# P-FTINT-2-0.net
KiCad netlist of a schematic drawn in Altium Designer
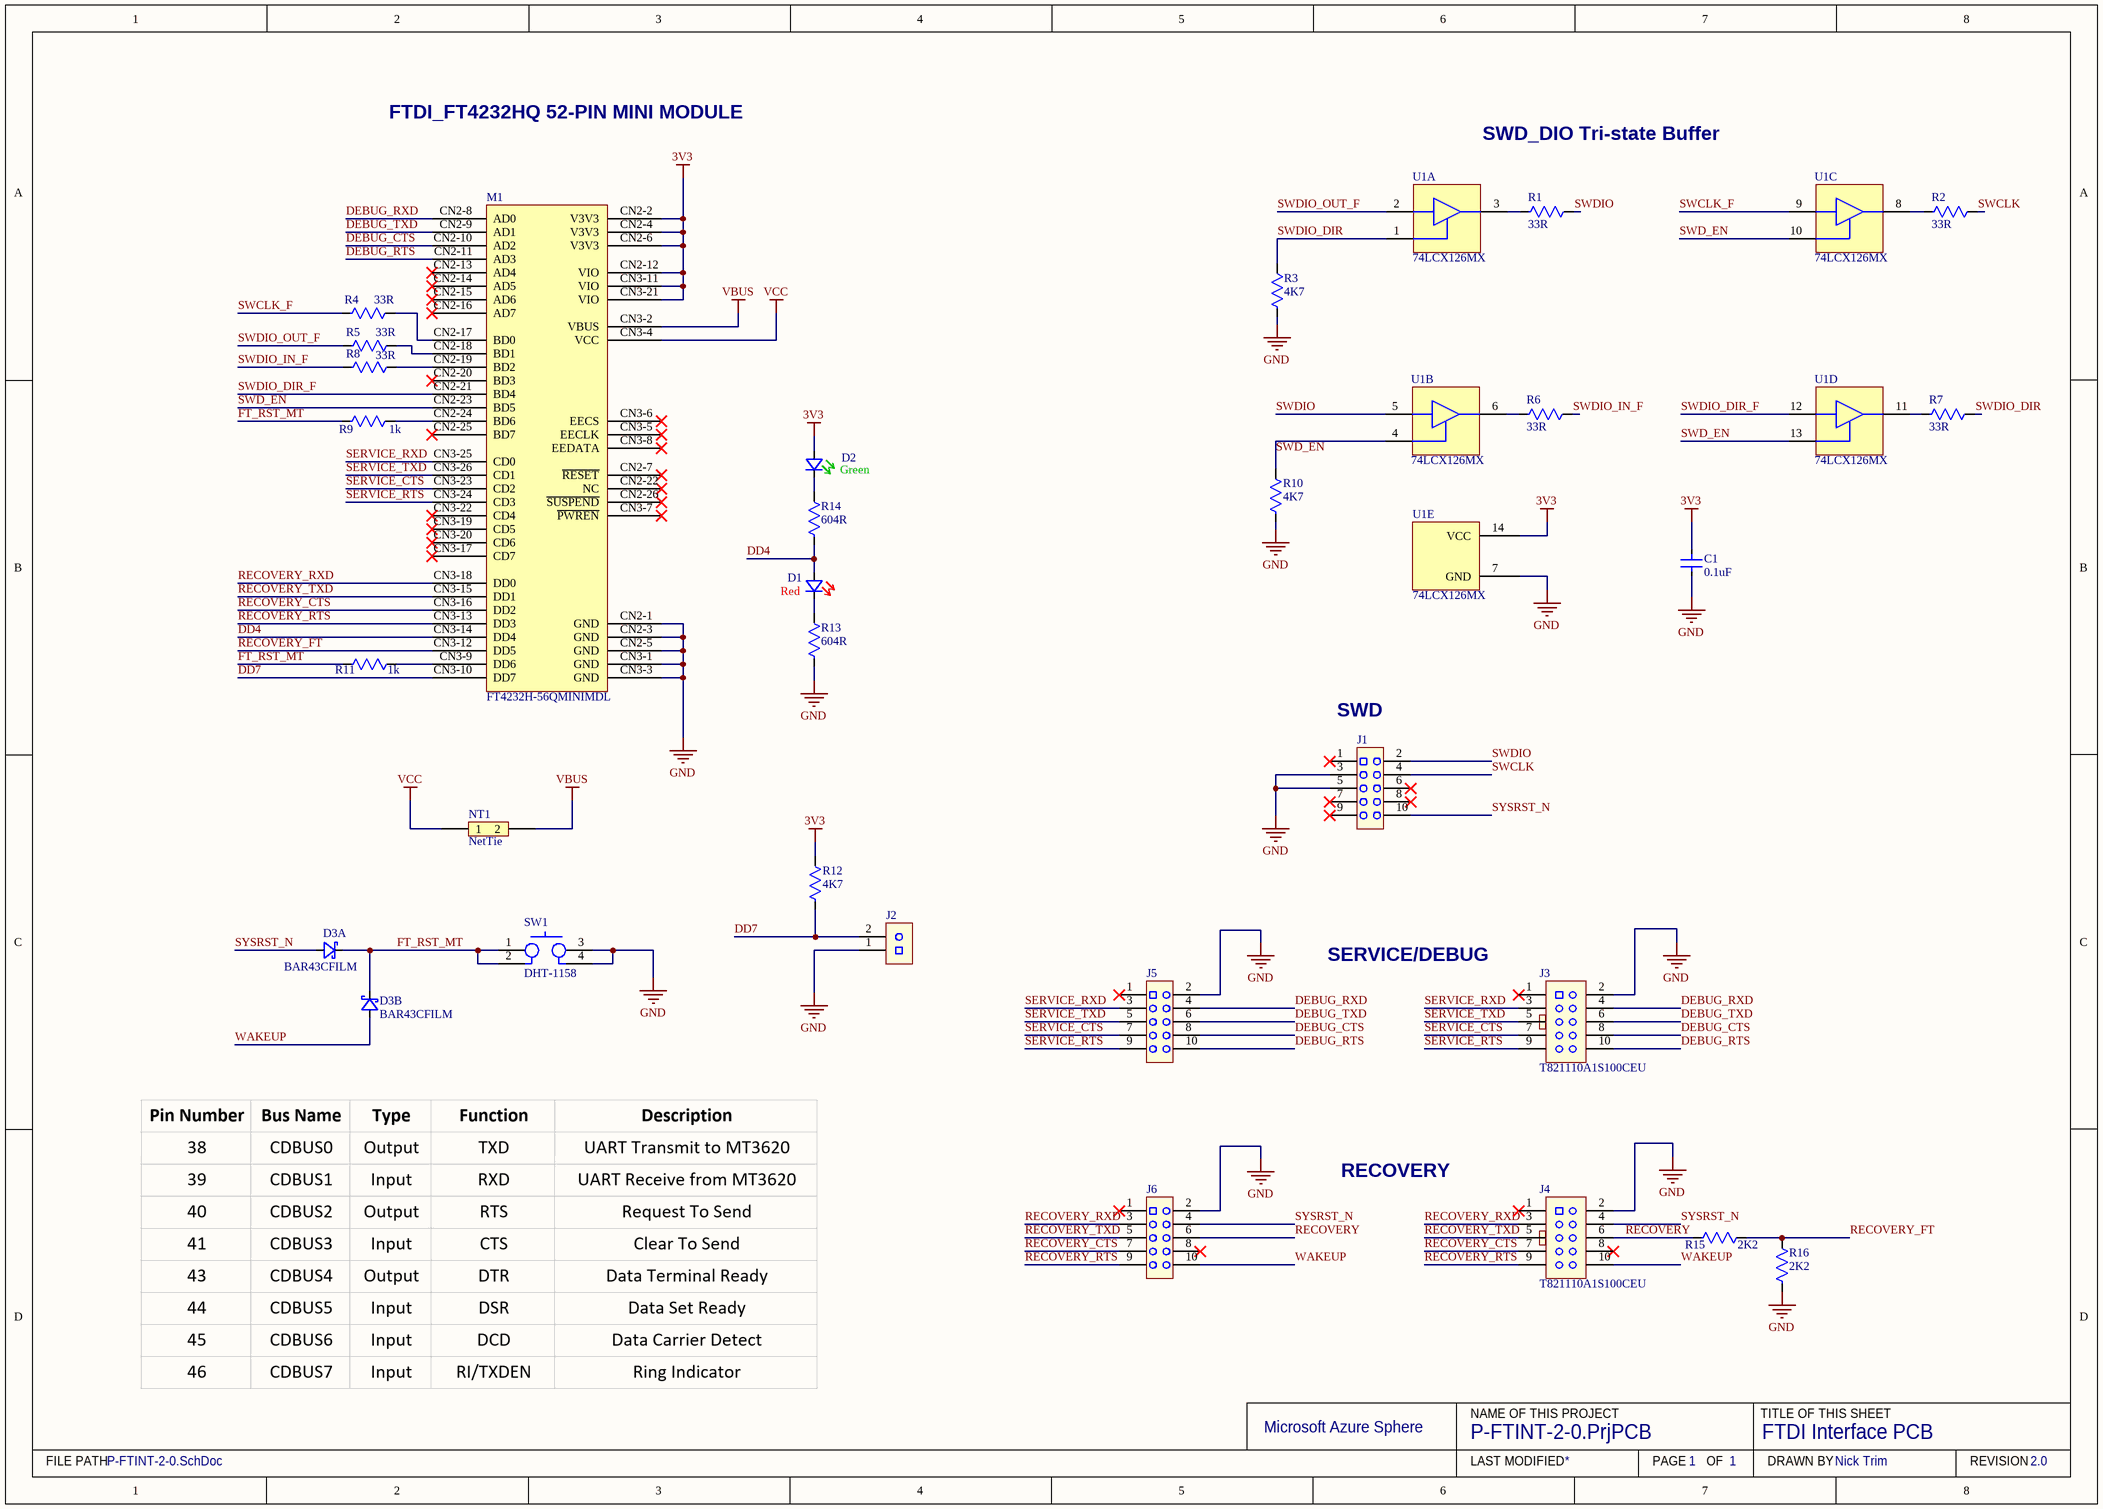
[diagram p0: P-FTINT-2-0.SchDoc]

(export (version "E")
  (design (tool "Eeschema 10.0.6"))
  (components
    (comp (ref "C1")
      (value "0.1uF")
      (footprint "CAP 0603 (1608) x 1.2mm")
      (description "CAP CER 0.1UF 25V X7R 0603")
      (fields
        (field (name "MANUFACTURER") "TDK")
        (field (name "MANUFACTURER PART NUMBER") "CGA3E2X7R1E104K080AA")
      )
      (libsource (lib "TDK-Capacitor_C_0603") (part "CGA3E2X7R1E104K080AA"))
    )
    (comp (ref "D1")
      (value "SML-D12U")
      (footprint "Rohm SML-D12 Red")
      (description "1.6 x 0.8 x 0.55mm (0603) LED 620nm Red")
      (fields
        (field (name "MANUFACTURER") "Rohm Semiconductor")
        (field (name "MANUFACTURER PART NUMBER") "SML-D12U8WT86")
        (field (name "COLOUR") "Red")
      )
      (libsource (lib "Rohm") (part "SML-D12U"))
    )
    (comp (ref "D2")
      (value "SML-D12P")
      (footprint "Rohm SML-D12 Green")
      (description "1.6 x 0.8 x 0.55mm (0603) LED 560nm Green")
      (fields
        (field (name "MANUFACTURER") "Rohm Semiconductor")
        (field (name "MANUFACTURER PART NUMBER") "SML-D12P8WT86")
        (field (name "COLOUR") "Green")
      )
      (libsource (lib "Rohm") (part "SML-D12P"))
    )
    (comp (ref "D3")
      (value "BAR43CFILM")
      (footprint "ON_SEMI-SOT23-3")
      (description "Small Signal Schottky Diode, Dual Common Cathode, 30 V, 100 mA, 330 mV, 750 mA, 150 °C")
      (fields (field (name "MANUFACTURER") "STMicroelectronics"))
      (libsource (lib "ST") (part "BAR43CFILM"))
    )
    (comp (ref "J1")
      (value "FTSH-105-01-F-DV-K")
      (footprint "SAMTEC-FTSH-105-01-X-DV-K")
      (description "CONN HEADER 10POS DUAL .05\" SMD")
      (fields (field (name "MANUFACTURER") "Samtec Inc."))
      (libsource (lib "Samtec") (part "FTSH-105-01-F-DV-K"))
    )
    (comp (ref "J2")
      (value "MOLEX-0022284020")
      (footprint "0022284020")
      (description "CONN HEADER 2POS .100 VERT TIN")
      (fields
        (field (name "MANUFACTURER") "Molex, LLC")
        (field (name "MANUFACTURER PART NUMBER") "0022284020")
      )
      (libsource (lib "Molex") (part "MOLEX-0022284020"))
    )
    (comp (ref "J3")
      (value "T821110A1S100CEU")
      (footprint "10 way shrouded IDC HDR:10 Way shrouded IDC hdr")
      (description "Conn Shrouded Header HDR 10 POS 2.54mm Solder ST Thru-Hole")
      (fields
        (field (name "MANUFACTURER") "Amphenol")
        (field (name "MANUFACTURER PART NUMBER") "T821110A1S100CEU")
      )
      (libsource (lib "Amphenol") (part "T821110A1S100CEU"))
    )
    (comp (ref "J4")
      (value "T821110A1S100CEU")
      (footprint "10 way shrouded IDC HDR:10 Way shrouded IDC hdr")
      (description "Conn Shrouded Header HDR 10 POS 2.54mm Solder ST Thru-Hole")
      (fields
        (field (name "MANUFACTURER") "Amphenol")
        (field (name "MANUFACTURER PART NUMBER") "T821110A1S100CEU")
      )
      (libsource (lib "Amphenol") (part "T821110A1S100CEU"))
    )
    (comp (ref "J5")
      (value "FTSH-105-01-F-DV-K")
      (footprint "SAMTEC-FTSH-105-01-X-DV-K")
      (description "CONN HEADER 10POS DUAL .05\" SMD")
      (fields (field (name "MANUFACTURER") "Samtec Inc."))
      (libsource (lib "Samtec") (part "FTSH-105-01-F-DV-K"))
    )
    (comp (ref "J6")
      (value "FTSH-105-01-F-DV-K")
      (footprint "SAMTEC-FTSH-105-01-X-DV-K")
      (description "CONN HEADER 10POS DUAL .05\" SMD")
      (fields (field (name "MANUFACTURER") "Samtec Inc."))
      (libsource (lib "Samtec") (part "FTSH-105-01-F-DV-K"))
    )
    (comp (ref "M1")
      (value "FT4232H-56QMINIMDL")
      (footprint "FT4232H-56Q")
      (description "IC MINI MODULE USB/FIFO 56QFN")
      (fields (field (name "MANUFACTURER") "FTDI"))
      (libsource (lib "FTDI") (part "FT4232H-56QMINIMDL"))
    )
    (comp (ref "NT1") (value "NetTie") (footprint "NetTie") (libsource (lib "generic") (part "NetTie")))
    (comp (ref "R1")
      (value "33R")
      (footprint "RES0603")
      (description "RES SMD 33 OHM 5% 1/10W 0603")
      (fields
        (field (name "MANUFACTURER") "Panasonic")
        (field (name "MANUFACTURER PART NUMBER") "ERJ-3GEYJ330V")
      )
      (libsource (lib "Panasonic_Resistor_ERJ3GR_0603") (part "ERJ-3GEYJ330V"))
    )
    (comp (ref "R2")
      (value "33R")
      (footprint "RES0603")
      (description "RES SMD 33 OHM 5% 1/10W 0603")
      (fields
        (field (name "MANUFACTURER") "Panasonic")
        (field (name "MANUFACTURER PART NUMBER") "ERJ-3GEYJ330V")
      )
      (libsource (lib "Panasonic_Resistor_ERJ3GR_0603") (part "ERJ-3GEYJ330V"))
    )
    (comp (ref "R3")
      (value "4K7")
      (footprint "RES0603")
      (description "RES SMD 4.7K OHM 5% 1/10W 0603")
      (fields
        (field (name "MANUFACTURER") "Panasonic")
        (field (name "MANUFACTURER PART NUMBER") "ERJ-3GEYJ472V")
      )
      (libsource (lib "Panasonic_Resistor_ERJ3GR_0603") (part "ERJ-3GEYJ472V"))
    )
    (comp (ref "R4")
      (value "33R")
      (footprint "RES0603")
      (description "RES SMD 33 OHM 5% 1/10W 0603")
      (fields
        (field (name "MANUFACTURER") "Panasonic")
        (field (name "MANUFACTURER PART NUMBER") "ERJ-3GEYJ330V")
      )
      (libsource (lib "Panasonic_Resistor_ERJ3GR_0603") (part "ERJ-3GEYJ330V"))
    )
    (comp (ref "R5")
      (value "33R")
      (footprint "RES0603")
      (description "RES SMD 33 OHM 5% 1/10W 0603")
      (fields
        (field (name "MANUFACTURER") "Panasonic")
        (field (name "MANUFACTURER PART NUMBER") "ERJ-3GEYJ330V")
      )
      (libsource (lib "Panasonic_Resistor_ERJ3GR_0603") (part "ERJ-3GEYJ330V"))
    )
    (comp (ref "R6")
      (value "33R")
      (footprint "RES0603")
      (description "RES SMD 33 OHM 5% 1/10W 0603")
      (fields
        (field (name "MANUFACTURER") "Panasonic")
        (field (name "MANUFACTURER PART NUMBER") "ERJ-3GEYJ330V")
      )
      (libsource (lib "Panasonic_Resistor_ERJ3GR_0603") (part "ERJ-3GEYJ330V"))
    )
    (comp (ref "R7")
      (value "33R")
      (footprint "RES0603")
      (description "RES SMD 33 OHM 5% 1/10W 0603")
      (fields
        (field (name "MANUFACTURER") "Panasonic")
        (field (name "MANUFACTURER PART NUMBER") "ERJ-3GEYJ330V")
      )
      (libsource (lib "Panasonic_Resistor_ERJ3GR_0603") (part "ERJ-3GEYJ330V"))
    )
    (comp (ref "R8")
      (value "33R")
      (footprint "RES0603")
      (description "RES SMD 33 OHM 5% 1/10W 0603")
      (fields
        (field (name "MANUFACTURER") "Panasonic")
        (field (name "MANUFACTURER PART NUMBER") "ERJ-3GEYJ330V")
      )
      (libsource (lib "Panasonic_Resistor_ERJ3GR_0603") (part "ERJ-3GEYJ330V"))
    )
    (comp (ref "R9")
      (value "ERJ-PA3J102V")
      (footprint "RES0603")
      (description "RES SMD 1K OHM 5% 1/10W 0603")
      (fields
        (field (name "MANUFACTURER") "Panasonic")
        (field (name "RESISTANCE") "1k")
        (field (name "TOLERANCE") "5%")
      )
      (libsource (lib "Panasonic_Resistor_ERJ3GR_0603") (part "ERJ-PA3J102V"))
    )
    (comp (ref "R10")
      (value "4K7")
      (footprint "RES0603")
      (description "RES SMD 4.7K OHM 5% 1/10W 0603")
      (fields
        (field (name "MANUFACTURER") "Panasonic")
        (field (name "MANUFACTURER PART NUMBER") "ERJ-3GEYJ472V")
      )
      (libsource (lib "Panasonic_Resistor_ERJ3GR_0603") (part "ERJ-3GEYJ472V"))
    )
    (comp (ref "R11")
      (value "ERJ-PA3J102V")
      (footprint "RES0603")
      (description "RES SMD 1K OHM 5% 1/10W 0603")
      (fields
        (field (name "MANUFACTURER") "Panasonic")
        (field (name "RESISTANCE") "1k")
        (field (name "TOLERANCE") "5%")
      )
      (libsource (lib "Panasonic_Resistor_ERJ3GR_0603") (part "ERJ-PA3J102V"))
    )
    (comp (ref "R12")
      (value "4K7")
      (footprint "RES0603")
      (description "RES SMD 4.7K OHM 5% 1/10W 0603")
      (fields
        (field (name "MANUFACTURER") "Panasonic")
        (field (name "MANUFACTURER PART NUMBER") "ERJ-3GEYJ472V")
      )
      (libsource (lib "Panasonic_Resistor_ERJ3GR_0603") (part "ERJ-3GEYJ472V"))
    )
    (comp (ref "R13")
      (value "604R")
      (footprint "RES0603")
      (description "RES SMD 604 OHM 1% 1/10W 0603")
      (fields
        (field (name "MANUFACTURER") "Panasonic")
        (field (name "MANUFACTURER PART NUMBER") "ERJ-3EKF6040V")
      )
      (libsource (lib "Panasonic_Resistor_ERJ3GR_0603") (part "ERJ-3EKF6040V"))
    )
    (comp (ref "R14")
      (value "604R")
      (footprint "RES0603")
      (description "RES SMD 604 OHM 1% 1/10W 0603")
      (fields
        (field (name "MANUFACTURER") "Panasonic")
        (field (name "MANUFACTURER PART NUMBER") "ERJ-3EKF6040V")
      )
      (libsource (lib "Panasonic_Resistor_ERJ3GR_0603") (part "ERJ-3EKF6040V"))
    )
    (comp (ref "R15")
      (value "2K2")
      (footprint "RES0603")
      (description "RES SMD 2.2K OHM 5% 1/10W 0603")
      (fields
        (field (name "MANUFACTURER") "Panasonic")
        (field (name "MANUFACTURER PART NUMBER") "ERJ-3GEYJ222V")
      )
      (libsource (lib "Panasonic_Resistor_ERJ3GR_0603") (part "ERJ-3GEYJ222V"))
    )
    (comp (ref "R16")
      (value "2K2")
      (footprint "RES0603")
      (description "RES SMD 2.2K OHM 5% 1/10W 0603")
      (fields
        (field (name "MANUFACTURER") "Panasonic")
        (field (name "MANUFACTURER PART NUMBER") "ERJ-3GEYJ222V")
      )
      (libsource (lib "Panasonic_Resistor_ERJ3GR_0603") (part "ERJ-3GEYJ222V"))
    )
    (comp (ref "SW1") (value "DHT-1158") (footprint "DHT-1158") (libsource (lib "Seeed") (part "DHT-1158")))
    (comp (ref "U1")
      (value "74LCX126MX")
      (footprint "74LCX126MX")
      (description "Buffers & Line Drivers LV Quad Buffer 5V Tolerant I/O")
      (fields (field (name "MANUFACTURER") "ON Semiconductor / Fairchild"))
      (libsource (lib "OnSemiconductor") (part "74LCX126MX"))
    )
  )
  (nets
    (net (code "1") (name "/DD4") (class "Default")
      (node (ref "D1") (pin "2") (pinfunction "A_2") (pintype "passive"))
      (node (ref "M1") (pin "CN3-14") (pinfunction "DD4_CN3-14") (pintype "passive"))
      (node (ref "R14") (pin "2") (pinfunction "2_2") (pintype "passive"))
    )
    (net (code "2") (name "/DD7") (class "Default")
      (node (ref "J2") (pin "2") (pinfunction "2_2") (pintype "passive"))
      (node (ref "M1") (pin "CN3-10") (pinfunction "DD7_CN3-10") (pintype "passive"))
      (node (ref "R12") (pin "2") (pinfunction "2_2") (pintype "passive"))
    )
    (net (code "3") (name "/DEBUG_CTS") (class "Default")
      (node (ref "J3") (pin "8") (pinfunction "8_8") (pintype "passive"))
      (node (ref "J5") (pin "8") (pinfunction "8_8") (pintype "passive"))
      (node (ref "M1") (pin "CN2-10") (pinfunction "AD2_CN2-10") (pintype "passive"))
    )
    (net (code "4") (name "/DEBUG_RTS") (class "Default")
      (node (ref "J3") (pin "10") (pinfunction "10_10") (pintype "passive"))
      (node (ref "J5") (pin "10") (pinfunction "10_10") (pintype "passive"))
      (node (ref "M1") (pin "CN2-11") (pinfunction "AD3_CN2-11") (pintype "passive"))
    )
    (net (code "5") (name "/DEBUG_RXD") (class "Default")
      (node (ref "J3") (pin "4") (pinfunction "4_4") (pintype "passive"))
      (node (ref "J5") (pin "4") (pinfunction "4_4") (pintype "passive"))
      (node (ref "M1") (pin "CN2-8") (pinfunction "AD0_CN2-8") (pintype "passive"))
    )
    (net (code "6") (name "/DEBUG_TXD") (class "Default")
      (node (ref "J3") (pin "6") (pinfunction "6_6") (pintype "passive"))
      (node (ref "J5") (pin "6") (pinfunction "6_6") (pintype "passive"))
      (node (ref "M1") (pin "CN2-9") (pinfunction "AD1_CN2-9") (pintype "passive"))
    )
    (net (code "7") (name "/FT_RST_MT") (class "Default")
      (node (ref "D3") (pin "3") (pinfunction "K_3") (pintype "passive"))
      (node (ref "R11") (pin "2") (pinfunction "2_2") (pintype "passive"))
      (node (ref "R9") (pin "2") (pinfunction "2_2") (pintype "passive"))
      (node (ref "SW1") (pin "1") (pinfunction "1_1") (pintype "passive"))
      (node (ref "SW1") (pin "2") (pinfunction "2_2") (pintype "passive"))
    )
    (net (code "8") (name "/RECOVERY") (class "Default")
      (node (ref "J4") (pin "6") (pinfunction "6_6") (pintype "passive"))
      (node (ref "J6") (pin "6") (pinfunction "6_6") (pintype "passive"))
      (node (ref "R15") (pin "2") (pinfunction "2_2") (pintype "passive"))
    )
    (net (code "9") (name "/RECOVERY_CTS") (class "Default")
      (node (ref "J4") (pin "7") (pinfunction "7_7") (pintype "passive"))
      (node (ref "J6") (pin "7") (pinfunction "7_7") (pintype "passive"))
      (node (ref "M1") (pin "CN3-16") (pinfunction "DD2_CN3-16") (pintype "passive"))
    )
    (net (code "10") (name "/RECOVERY_FT") (class "Default")
      (node (ref "M1") (pin "CN3-12") (pinfunction "DD5_CN3-12") (pintype "passive"))
      (node (ref "R15") (pin "1") (pinfunction "1_1") (pintype "passive"))
      (node (ref "R16") (pin "1") (pinfunction "1_1") (pintype "passive"))
    )
    (net (code "11") (name "/RECOVERY_RTS") (class "Default")
      (node (ref "J4") (pin "9") (pinfunction "9_9") (pintype "passive"))
      (node (ref "J6") (pin "9") (pinfunction "9_9") (pintype "passive"))
      (node (ref "M1") (pin "CN3-13") (pinfunction "DD3_CN3-13") (pintype "passive"))
    )
    (net (code "12") (name "/RECOVERY_RXD") (class "Default")
      (node (ref "J4") (pin "3") (pinfunction "3_3") (pintype "passive"))
      (node (ref "J6") (pin "3") (pinfunction "3_3") (pintype "passive"))
      (node (ref "M1") (pin "CN3-18") (pinfunction "DD0_CN3-18") (pintype "passive"))
    )
    (net (code "13") (name "/RECOVERY_TXD") (class "Default")
      (node (ref "J4") (pin "5") (pinfunction "5_5") (pintype "passive"))
      (node (ref "J6") (pin "5") (pinfunction "5_5") (pintype "passive"))
      (node (ref "M1") (pin "CN3-15") (pinfunction "DD1_CN3-15") (pintype "passive"))
    )
    (net (code "14") (name "/SERVICE_CTS") (class "Default")
      (node (ref "J3") (pin "7") (pinfunction "7_7") (pintype "passive"))
      (node (ref "J5") (pin "7") (pinfunction "7_7") (pintype "passive"))
      (node (ref "M1") (pin "CN3-23") (pinfunction "CD2_CN3-23") (pintype "passive"))
    )
    (net (code "15") (name "/SERVICE_RTS") (class "Default")
      (node (ref "J3") (pin "9") (pinfunction "9_9") (pintype "passive"))
      (node (ref "J5") (pin "9") (pinfunction "9_9") (pintype "passive"))
      (node (ref "M1") (pin "CN3-24") (pinfunction "CD3_CN3-24") (pintype "passive"))
    )
    (net (code "16") (name "/SERVICE_RXD") (class "Default")
      (node (ref "J3") (pin "3") (pinfunction "3_3") (pintype "passive"))
      (node (ref "J5") (pin "3") (pinfunction "3_3") (pintype "passive"))
      (node (ref "M1") (pin "CN3-25") (pinfunction "CD0_CN3-25") (pintype "passive"))
    )
    (net (code "17") (name "/SERVICE_TXD") (class "Default")
      (node (ref "J3") (pin "5") (pinfunction "5_5") (pintype "passive"))
      (node (ref "J5") (pin "5") (pinfunction "5_5") (pintype "passive"))
      (node (ref "M1") (pin "CN3-26") (pinfunction "CD1_CN3-26") (pintype "passive"))
    )
    (net (code "18") (name "/SWCLK") (class "Default")
      (node (ref "J1") (pin "4") (pinfunction "4_4") (pintype "passive"))
      (node (ref "R2") (pin "1") (pinfunction "1_1") (pintype "passive"))
    )
    (net (code "19") (name "/SWCLK_F") (class "Default")
      (node (ref "R4") (pin "2") (pinfunction "2_2") (pintype "passive"))
      (node (ref "U1") (pin "9") (pinfunction "3A_9") (pintype "passive"))
    )
    (net (code "20") (name "/SWDIO") (class "Default")
      (node (ref "J1") (pin "2") (pinfunction "2_2") (pintype "passive"))
      (node (ref "R1") (pin "1") (pinfunction "1_1") (pintype "passive"))
      (node (ref "U1") (pin "5") (pinfunction "2A_5") (pintype "passive"))
    )
    (net (code "21") (name "/SWDIO_DIR") (class "Default")
      (node (ref "R3") (pin "1") (pinfunction "1_1") (pintype "passive"))
      (node (ref "R7") (pin "1") (pinfunction "1_1") (pintype "passive"))
      (node (ref "U1") (pin "1") (pinfunction "1OE_1") (pintype "passive"))
    )
    (net (code "22") (name "/SWDIO_DIR_F") (class "Default")
      (node (ref "M1") (pin "CN2-21") (pinfunction "BD4_CN2-21") (pintype "passive"))
      (node (ref "U1") (pin "12") (pinfunction "4A_12") (pintype "passive"))
    )
    (net (code "23") (name "/SWDIO_IN_F") (class "Default")
      (node (ref "R6") (pin "1") (pinfunction "1_1") (pintype "passive"))
      (node (ref "R8") (pin "2") (pinfunction "2_2") (pintype "passive"))
    )
    (net (code "24") (name "/SWDIO_OUT_F") (class "Default")
      (node (ref "R5") (pin "2") (pinfunction "2_2") (pintype "passive"))
      (node (ref "U1") (pin "2") (pinfunction "1A_2") (pintype "passive"))
    )
    (net (code "25") (name "/SWD_EN") (class "Default")
      (node (ref "M1") (pin "CN2-23") (pinfunction "BD5_CN2-23") (pintype "passive"))
      (node (ref "R10") (pin "1") (pinfunction "1_1") (pintype "passive"))
      (node (ref "U1") (pin "10") (pinfunction "3OE_10") (pintype "passive"))
      (node (ref "U1") (pin "13") (pinfunction "4OE_13") (pintype "passive"))
      (node (ref "U1") (pin "4") (pinfunction "2OE_4") (pintype "passive"))
    )
    (net (code "26") (name "/SYSRST_N") (class "Default")
      (node (ref "D3") (pin "1") (pinfunction "A1_1") (pintype "passive"))
      (node (ref "J1") (pin "10") (pinfunction "10_10") (pintype "passive"))
      (node (ref "J4") (pin "4") (pinfunction "4_4") (pintype "passive"))
      (node (ref "J6") (pin "4") (pinfunction "4_4") (pintype "passive"))
    )
    (net (code "27") (name "/WAKEUP") (class "Default")
      (node (ref "D3") (pin "2") (pinfunction "A2_2") (pintype "passive"))
      (node (ref "J4") (pin "10") (pinfunction "10_10") (pintype "passive"))
      (node (ref "J6") (pin "10") (pinfunction "10_10") (pintype "passive"))
    )
    (net (code "28") (name "3V3") (class "Default")
      (node (ref "C1") (pin "2") (pinfunction "2_2") (pintype "passive"))
      (node (ref "D2") (pin "2") (pinfunction "A_2") (pintype "passive"))
      (node (ref "M1") (pin "CN2-12") (pinfunction "VIO_CN2-12") (pintype "passive"))
      (node (ref "M1") (pin "CN2-2") (pinfunction "V3V3_CN2-2") (pintype "passive"))
      (node (ref "M1") (pin "CN2-4") (pinfunction "V3V3_CN2-4") (pintype "passive"))
      (node (ref "M1") (pin "CN2-6") (pinfunction "V3V3_CN2-6") (pintype "passive"))
      (node (ref "M1") (pin "CN3-11") (pinfunction "VIO_CN3-11") (pintype "passive"))
      (node (ref "M1") (pin "CN3-21") (pinfunction "VIO_CN3-21") (pintype "passive"))
      (node (ref "R12") (pin "1") (pinfunction "1_1") (pintype "passive"))
      (node (ref "U1") (pin "14") (pinfunction "VCC_14") (pintype "passive"))
    )
    (net (code "29") (name "GND") (class "Default")
      (node (ref "C1") (pin "1") (pinfunction "1_1") (pintype "passive"))
      (node (ref "J1") (pin "3") (pinfunction "3_3") (pintype "passive"))
      (node (ref "J1") (pin "5") (pinfunction "5_5") (pintype "passive"))
      (node (ref "J2") (pin "1") (pinfunction "1_1") (pintype "passive"))
      (node (ref "J3") (pin "2") (pinfunction "2_2") (pintype "passive"))
      (node (ref "J4") (pin "2") (pinfunction "2_2") (pintype "passive"))
      (node (ref "J5") (pin "2") (pinfunction "2_2") (pintype "passive"))
      (node (ref "J6") (pin "2") (pinfunction "2_2") (pintype "passive"))
      (node (ref "M1") (pin "CN2-1") (pinfunction "GND_CN2-1") (pintype "passive"))
      (node (ref "M1") (pin "CN2-3") (pinfunction "GND_CN2-3") (pintype "passive"))
      (node (ref "M1") (pin "CN2-5") (pinfunction "GND_CN2-5") (pintype "passive"))
      (node (ref "M1") (pin "CN3-1") (pinfunction "GND_CN3-1") (pintype "passive"))
      (node (ref "M1") (pin "CN3-3") (pinfunction "GND_CN3-3") (pintype "passive"))
      (node (ref "R10") (pin "2") (pinfunction "2_2") (pintype "passive"))
      (node (ref "R13") (pin "2") (pinfunction "2_2") (pintype "passive"))
      (node (ref "R16") (pin "2") (pinfunction "2_2") (pintype "passive"))
      (node (ref "R3") (pin "2") (pinfunction "2_2") (pintype "passive"))
      (node (ref "SW1") (pin "3") (pinfunction "3_3") (pintype "passive"))
      (node (ref "SW1") (pin "4") (pinfunction "4_4") (pintype "passive"))
      (node (ref "U1") (pin "7") (pinfunction "GND_7") (pintype "power_in"))
    )
    (net (code "30") (name "Net-(D1-K)") (class "Default")
      (node (ref "D1") (pin "1") (pinfunction "K_1") (pintype "passive"))
      (node (ref "R13") (pin "1") (pinfunction "1_1") (pintype "passive"))
    )
    (net (code "31") (name "Net-(D2-K)") (class "Default")
      (node (ref "D2") (pin "1") (pinfunction "K_1") (pintype "passive"))
      (node (ref "R14") (pin "1") (pinfunction "1_1") (pintype "passive"))
    )
    (net (code "32") (name "Net-(M1-BD0)") (class "Default")
      (node (ref "M1") (pin "CN2-17") (pinfunction "BD0_CN2-17") (pintype "passive"))
      (node (ref "R4") (pin "1") (pinfunction "1_1") (pintype "passive"))
    )
    (net (code "33") (name "Net-(M1-BD1)") (class "Default")
      (node (ref "M1") (pin "CN2-18") (pinfunction "BD1_CN2-18") (pintype "passive"))
      (node (ref "R5") (pin "1") (pinfunction "1_1") (pintype "passive"))
    )
    (net (code "34") (name "Net-(M1-BD2)") (class "Default")
      (node (ref "M1") (pin "CN2-19") (pinfunction "BD2_CN2-19") (pintype "passive"))
      (node (ref "R8") (pin "1") (pinfunction "1_1") (pintype "passive"))
    )
    (net (code "35") (name "Net-(M1-BD6)") (class "Default")
      (node (ref "M1") (pin "CN2-24") (pinfunction "BD6_CN2-24") (pintype "passive"))
      (node (ref "R9") (pin "1") (pinfunction "1_1") (pintype "passive"))
    )
    (net (code "36") (name "Net-(M1-DD6)") (class "Default")
      (node (ref "M1") (pin "CN3-9") (pinfunction "DD6_CN3-9") (pintype "passive"))
      (node (ref "R11") (pin "1") (pinfunction "1_1") (pintype "passive"))
    )
    (net (code "37") (name "Net-(U1A-1Y)") (class "Default")
      (node (ref "R1") (pin "2") (pinfunction "2_2") (pintype "passive"))
      (node (ref "U1") (pin "3") (pinfunction "1Y_3") (pintype "passive"))
    )
    (net (code "38") (name "Net-(U1B-2Y)") (class "Default")
      (node (ref "R6") (pin "2") (pinfunction "2_2") (pintype "passive"))
      (node (ref "U1") (pin "6") (pinfunction "2Y_6") (pintype "passive"))
    )
    (net (code "39") (name "Net-(U1C-3Y)") (class "Default")
      (node (ref "R2") (pin "2") (pinfunction "2_2") (pintype "passive"))
      (node (ref "U1") (pin "8") (pinfunction "3Y_8") (pintype "passive"))
    )
    (net (code "40") (name "Net-(U1D-4Y)") (class "Default")
      (node (ref "R7") (pin "2") (pinfunction "2_2") (pintype "passive"))
      (node (ref "U1") (pin "11") (pinfunction "4Y_11") (pintype "passive"))
    )
    (net (code "41") (name "VBUS") (class "Default")
      (node (ref "M1") (pin "CN3-2") (pinfunction "VBUS_CN3-2") (pintype "passive"))
      (node (ref "NT1") (pin "2") (pinfunction "2_2") (pintype "passive"))
    )
    (net (code "42") (name "VCC") (class "Default")
      (node (ref "M1") (pin "CN3-4") (pinfunction "VCC_CN3-4") (pintype "passive"))
      (node (ref "NT1") (pin "1") (pinfunction "1_1") (pintype "passive"))
    )
    (net (code "43") (name "unconnected-(J1-Pad1)") (class "Default")
      (node (ref "J1") (pin "1") (pinfunction "1_1") (pintype "passive+no_connect"))
    )
    (net (code "44") (name "unconnected-(J1-Pad6)") (class "Default")
      (node (ref "J1") (pin "6") (pinfunction "6_6") (pintype "passive+no_connect"))
    )
    (net (code "45") (name "unconnected-(J1-Pad7)") (class "Default")
      (node (ref "J1") (pin "7") (pinfunction "7_7") (pintype "passive+no_connect"))
    )
    (net (code "46") (name "unconnected-(J1-Pad8)") (class "Default")
      (node (ref "J1") (pin "8") (pinfunction "8_8") (pintype "passive+no_connect"))
    )
    (net (code "47") (name "unconnected-(J1-Pad9)") (class "Default")
      (node (ref "J1") (pin "9") (pinfunction "9_9") (pintype "passive+no_connect"))
    )
    (net (code "48") (name "unconnected-(J3-Pad1)") (class "Default")
      (node (ref "J3") (pin "1") (pinfunction "1_1") (pintype "passive+no_connect"))
    )
    (net (code "49") (name "unconnected-(J4-Pad1)") (class "Default")
      (node (ref "J4") (pin "1") (pinfunction "1_1") (pintype "passive+no_connect"))
    )
    (net (code "50") (name "unconnected-(J4-Pad8)") (class "Default")
      (node (ref "J4") (pin "8") (pinfunction "8_8") (pintype "passive+no_connect"))
    )
    (net (code "51") (name "unconnected-(J5-Pad1)") (class "Default")
      (node (ref "J5") (pin "1") (pinfunction "1_1") (pintype "passive+no_connect"))
    )
    (net (code "52") (name "unconnected-(J6-Pad1)") (class "Default")
      (node (ref "J6") (pin "1") (pinfunction "1_1") (pintype "passive+no_connect"))
    )
    (net (code "53") (name "unconnected-(J6-Pad8)") (class "Default")
      (node (ref "J6") (pin "8") (pinfunction "8_8") (pintype "passive+no_connect"))
    )
    (net (code "54") (name "unconnected-(M1-AD4-PadCN2-13)") (class "Default")
      (node (ref "M1") (pin "CN2-13") (pinfunction "AD4_CN2-13") (pintype "passive+no_connect"))
    )
    (net (code "55") (name "unconnected-(M1-AD5-PadCN2-14)") (class "Default")
      (node (ref "M1") (pin "CN2-14") (pinfunction "AD5_CN2-14") (pintype "passive+no_connect"))
    )
    (net (code "56") (name "unconnected-(M1-AD6-PadCN2-15)") (class "Default")
      (node (ref "M1") (pin "CN2-15") (pinfunction "AD6_CN2-15") (pintype "passive+no_connect"))
    )
    (net (code "57") (name "unconnected-(M1-AD7-PadCN2-16)") (class "Default")
      (node (ref "M1") (pin "CN2-16") (pinfunction "AD7_CN2-16") (pintype "passive+no_connect"))
    )
    (net (code "58") (name "unconnected-(M1-BD3-PadCN2-20)") (class "Default")
      (node (ref "M1") (pin "CN2-20") (pinfunction "BD3_CN2-20") (pintype "passive+no_connect"))
    )
    (net (code "59") (name "unconnected-(M1-BD7-PadCN2-25)") (class "Default")
      (node (ref "M1") (pin "CN2-25") (pinfunction "BD7_CN2-25") (pintype "passive+no_connect"))
    )
    (net (code "60") (name "unconnected-(M1-CD4-PadCN3-22)") (class "Default")
      (node (ref "M1") (pin "CN3-22") (pinfunction "CD4_CN3-22") (pintype "passive+no_connect"))
    )
    (net (code "61") (name "unconnected-(M1-CD5-PadCN3-19)") (class "Default")
      (node (ref "M1") (pin "CN3-19") (pinfunction "CD5_CN3-19") (pintype "passive+no_connect"))
    )
    (net (code "62") (name "unconnected-(M1-CD6-PadCN3-20)") (class "Default")
      (node (ref "M1") (pin "CN3-20") (pinfunction "CD6_CN3-20") (pintype "passive+no_connect"))
    )
    (net (code "63") (name "unconnected-(M1-CD7-PadCN3-17)") (class "Default")
      (node (ref "M1") (pin "CN3-17") (pinfunction "CD7_CN3-17") (pintype "passive+no_connect"))
    )
    (net (code "64") (name "unconnected-(M1-EECLK-PadCN3-5)") (class "Default")
      (node (ref "M1") (pin "CN3-5") (pinfunction "EECLK_CN3-5") (pintype "passive+no_connect"))
    )
    (net (code "65") (name "unconnected-(M1-EECS-PadCN3-6)") (class "Default")
      (node (ref "M1") (pin "CN3-6") (pinfunction "EECS_CN3-6") (pintype "passive+no_connect"))
    )
    (net (code "66") (name "unconnected-(M1-EEDATA-PadCN3-8)") (class "Default")
      (node (ref "M1") (pin "CN3-8") (pinfunction "EEDATA_CN3-8") (pintype "passive+no_connect"))
    )
    (net (code "67") (name "unconnected-(M1-NC-PadCN2-22)") (class "Default")
      (node (ref "M1") (pin "CN2-22") (pinfunction "NC_CN2-22") (pintype "passive+no_connect"))
    )
    (net (code "68") (name "unconnected-(M1-~{PWREN}-PadCN3-7)") (class "Default")
      (node (ref "M1") (pin "CN3-7") (pinfunction "~{PWREN}_CN3-7") (pintype "passive+no_connect"))
    )
    (net (code "69") (name "unconnected-(M1-~{RESET}-PadCN2-7)") (class "Default")
      (node (ref "M1") (pin "CN2-7") (pinfunction "~{RESET}_CN2-7") (pintype "passive+no_connect"))
    )
    (net (code "70") (name "unconnected-(M1-~{SUSPEND}-PadCN2-26)") (class "Default")
      (node (ref "M1") (pin "CN2-26") (pinfunction "~{SUSPEND}_CN2-26") (pintype "passive+no_connect"))
    )
  )
)
